# E-P-204-R3.net
KiCad netlist of a schematic drawn in EAGLE
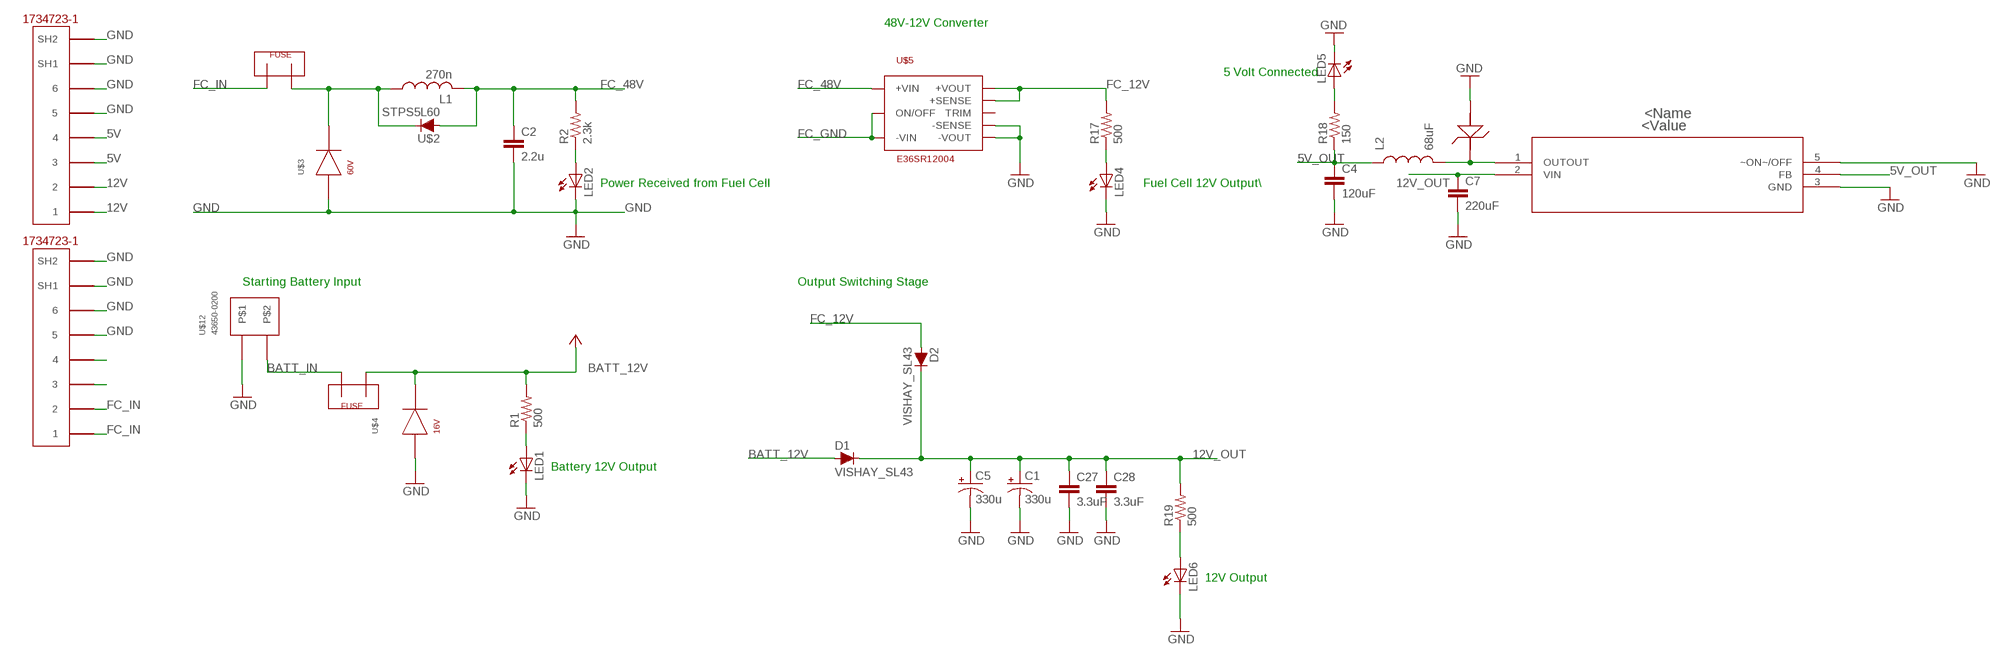
[diagram p0: schematic, sheet 1]

(export (version "E")
  (design (tool "Eeschema 10.0.6"))
  (components
    (comp (ref "C1")
      (value "330u")
      (footprint "eagle-import:PANASONIC_E")
      (libsource (lib "eagle-import") (part "CAP_POLE"))
    )
    (comp (ref "C2")
      (value "2.2u")
      (footprint "eagle-import:C1210")
      (libsource (lib "eagle-import") (part "C-EUC1210"))
    )
    (comp (ref "C4")
      (value "120uF")
      (footprint "eagle-import:0805")
      (libsource (lib "eagle-import") (part "CAP0805"))
    )
    (comp (ref "C5")
      (value "330u")
      (footprint "eagle-import:PANASONIC_E")
      (libsource (lib "eagle-import") (part "CAP_POLE"))
    )
    (comp (ref "C7")
      (value "220uF")
      (footprint "eagle-import:0805")
      (libsource (lib "eagle-import") (part "CAP0805"))
    )
    (comp (ref "C27")
      (value "3.3uF")
      (footprint "eagle-import:C0805K")
      (libsource (lib "eagle-import") (part "C-EUC0805K"))
    )
    (comp (ref "C28")
      (value "3.3uF")
      (footprint "eagle-import:C0805K")
      (libsource (lib "eagle-import") (part "C-EUC0805K"))
    )
    (comp (ref "D1")
      (value "VISHAY_SL43")
      (footprint "eagle-import:DO-214AB_SMC")
      (libsource (lib "eagle-import") (part "VISHAY_SL43"))
    )
    (comp (ref "D2")
      (value "VISHAY_SL43")
      (footprint "eagle-import:DO-214AB_SMC")
      (libsource (lib "eagle-import") (part "VISHAY_SL43"))
    )
    (comp (ref "L1")
      (value "270n")
      (footprint "eagle-import:L3225P")
      (libsource (lib "eagle-import") (part "L-USL3225P"))
    )
    (comp (ref "L2")
      (value "68uF")
      (footprint "eagle-import:0805")
      (libsource (lib "eagle-import") (part "INDUCTOR0805"))
    )
    (comp (ref "LED1")
      (value "LED1206")
      (footprint "eagle-import:LED-1206")
      (libsource (lib "eagle-import") (part "LED1206"))
    )
    (comp (ref "LED2")
      (value "LED1206")
      (footprint "eagle-import:LED-1206")
      (libsource (lib "eagle-import") (part "LED1206"))
    )
    (comp (ref "LED4")
      (value "LED1206")
      (footprint "eagle-import:LED-1206")
      (libsource (lib "eagle-import") (part "LED1206"))
    )
    (comp (ref "LED5")
      (value "LED1206")
      (footprint "eagle-import:LED-1206")
      (libsource (lib "eagle-import") (part "LED1206"))
    )
    (comp (ref "LED6")
      (value "LED1206")
      (footprint "eagle-import:LED-1206")
      (libsource (lib "eagle-import") (part "LED1206"))
    )
    (comp (ref "R1")
      (value "500")
      (footprint "eagle-import:M0805")
      (libsource (lib "eagle-import") (part "R-US_M0805"))
    )
    (comp (ref "R2")
      (value "2.3k")
      (footprint "eagle-import:M0805")
      (libsource (lib "eagle-import") (part "R-US_M0805"))
    )
    (comp (ref "R17")
      (value "500")
      (footprint "eagle-import:M0805")
      (libsource (lib "eagle-import") (part "R-US_M0805"))
    )
    (comp (ref "R18")
      (value "150")
      (footprint "eagle-import:M0805")
      (libsource (lib "eagle-import") (part "R-US_M0805"))
    )
    (comp (ref "R19")
      (value "500")
      (footprint "eagle-import:M0805")
      (libsource (lib "eagle-import") (part "R-US_M0805"))
    )
    (comp (ref "U$2")
      (value "STPS5L60")
      (footprint "eagle-import:STM_SMC")
      (libsource (lib "eagle-import") (part "STPS5L60"))
    )
    (comp (ref "U$3")
      (value "SMBJ60CA")
      (footprint "eagle-import:.277X.089")
      (libsource (lib "eagle-import") (part "SMBJ60CA"))
    )
    (comp (ref "U$4")
      (value "SMAJ16CA")
      (footprint "eagle-import:.25X.07")
      (libsource (lib "eagle-import") (part "SMAJ16CA"))
    )
    (comp (ref "U$5")
      (value "E36SR12004")
      (footprint "eagle-import:2.30X0.90X0.34")
      (libsource (lib "eagle-import") (part "E36SR12004"))
    )
    (comp (ref "U$6")
      (value "5555140-6")
      (footprint "eagle-import:1734723-1_RJ11")
      (libsource (lib "eagle-import") (part "5555140-6"))
    )
    (comp (ref "U$7")
      (value "FUSEMINI-BLADE")
      (footprint "eagle-import:MINI-BLADE-FUSE")
      (libsource (lib "eagle-import") (part "FUSEMINI-BLADE"))
    )
    (comp (ref "U$8")
      (value "LM2595T-5.0")
      (footprint "eagle-import:T05D")
      (fields
        (field (name "MANUFACTURER_PART_NUMBER") "LM2595T50")
        (field (name "COPYRIGHT") "Copyright C 2015 Accelerated Designs. All rights reserved")
      )
      (libsource (lib "eagle-import") (part "LM2595T-5.0"))
    )
    (comp (ref "U$9")
      (value "MURS120T3G")
      (footprint "eagle-import:MURS120T3G")
      (libsource (lib "eagle-import") (part "MURS120T3G"))
    )
    (comp (ref "U$10")
      (value "FUSEMINI-BLADE")
      (footprint "eagle-import:MINI-BLADE-FUSE")
      (libsource (lib "eagle-import") (part "FUSEMINI-BLADE"))
    )
    (comp (ref "U$11")
      (value "5555140-6")
      (footprint "eagle-import:1734723-1_RJ11")
      (libsource (lib "eagle-import") (part "5555140-6"))
    )
    (comp (ref "U$12")
      (value "43650-0200")
      (footprint "eagle-import:43650-0200")
      (libsource (lib "eagle-import") (part "43650-0200"))
    )
  )
  (nets
    (net (code "1") (name "+5V") (class "Default")
      (node (ref "D1") (pin "A") (pinfunction "A_A") (pintype "passive"))
      (node (ref "R1") (pin "2") (pinfunction "2_2") (pintype "passive"))
      (node (ref "U$10") (pin "OUT") (pinfunction "OUT_OUT") (pintype "bidirectional"))
      (node (ref "U$4") (pin "CATHODE") (pinfunction "CATHODE_CATHODE") (pintype "bidirectional"))
    )
    (net (code "2") (name "/5V") (class "Default")
      (node (ref "U$11") (pin "3") (pinfunction "3_3") (pintype "bidirectional"))
      (node (ref "U$11") (pin "4") (pinfunction "4_4") (pintype "bidirectional"))
    )
    (net (code "3") (name "/5V_OUT") (class "Default")
      (node (ref "C4") (pin "1") (pinfunction "1_1") (pintype "passive"))
      (node (ref "L2") (pin "1") (pinfunction "1_1") (pintype "passive"))
      (node (ref "R18") (pin "1") (pinfunction "1_1") (pintype "passive"))
      (node (ref "U$8") (pin "4") (pinfunction "FB_4") (pintype "passive"))
    )
    (net (code "4") (name "/12V") (class "Default")
      (node (ref "U$11") (pin "1") (pinfunction "1_1") (pintype "bidirectional"))
      (node (ref "U$11") (pin "2") (pinfunction "2_2") (pintype "bidirectional"))
    )
    (net (code "5") (name "/12V_OUT") (class "Default")
      (node (ref "C1") (pin "+") (pinfunction "+_+") (pintype "passive"))
      (node (ref "C27") (pin "1") (pinfunction "1_1") (pintype "passive"))
      (node (ref "C28") (pin "1") (pinfunction "1_1") (pintype "passive"))
      (node (ref "C5") (pin "+") (pinfunction "+_+") (pintype "passive"))
      (node (ref "C7") (pin "1") (pinfunction "1_1") (pintype "passive"))
      (node (ref "D1") (pin "C") (pinfunction "C_C") (pintype "passive"))
      (node (ref "D2") (pin "C") (pinfunction "C_C") (pintype "passive"))
      (node (ref "R19") (pin "2") (pinfunction "2_2") (pintype "passive"))
      (node (ref "U$8") (pin "2") (pinfunction "VIN_2") (pintype "input"))
    )
    (net (code "6") (name "/BATT_IN") (class "Default")
      (node (ref "U$10") (pin "IN") (pinfunction "IN_IN") (pintype "bidirectional"))
      (node (ref "U$12") (pin "P$1") (pinfunction "P$2_P$1") (pintype "bidirectional"))
    )
    (net (code "7") (name "/FC_12V") (class "Default")
      (node (ref "D2") (pin "A") (pinfunction "A_A") (pintype "passive"))
      (node (ref "R17") (pin "2") (pinfunction "2_2") (pintype "passive"))
      (node (ref "U$5") (pin "P$7") (pinfunction "+SENSE_P$7") (pintype "input"))
      (node (ref "U$5") (pin "P$8") (pinfunction "+VOUT_P$8") (pintype "power_in"))
    )
    (net (code "8") (name "/FC_48V") (class "Default")
      (node (ref "C2") (pin "1") (pinfunction "1_1") (pintype "passive"))
      (node (ref "L1") (pin "2") (pinfunction "2_2") (pintype "passive"))
      (node (ref "R2") (pin "2") (pinfunction "2_2") (pintype "passive"))
      (node (ref "U$2") (pin "A") (pinfunction "A_A") (pintype "passive"))
      (node (ref "U$5") (pin "P$1") (pinfunction "+VIN_P$1") (pintype "power_in"))
    )
    (net (code "9") (name "/FC_GND") (class "Default")
      (node (ref "U$5") (pin "P$2") (pinfunction "ON/OFF_P$2") (pintype "bidirectional"))
      (node (ref "U$5") (pin "P$3") (pinfunction "-VIN_P$3") (pintype "power_in"))
    )
    (net (code "10") (name "/FC_IN") (class "Default")
      (node (ref "U$6") (pin "1") (pinfunction "1_1") (pintype "bidirectional"))
      (node (ref "U$6") (pin "2") (pinfunction "2_2") (pintype "bidirectional"))
      (node (ref "U$7") (pin "OUT") (pinfunction "OUT_OUT") (pintype "bidirectional"))
    )
    (net (code "11") (name "GND") (class "Default")
      (node (ref "C1") (pin "-") (pinfunction "-_-") (pintype "passive"))
      (node (ref "C2") (pin "2") (pinfunction "2_2") (pintype "passive"))
      (node (ref "C27") (pin "2") (pinfunction "2_2") (pintype "passive"))
      (node (ref "C28") (pin "2") (pinfunction "2_2") (pintype "passive"))
      (node (ref "C4") (pin "2") (pinfunction "2_2") (pintype "passive"))
      (node (ref "C5") (pin "-") (pinfunction "-_-") (pintype "passive"))
      (node (ref "C7") (pin "2") (pinfunction "2_2") (pintype "passive"))
      (node (ref "LED1") (pin "C") (pinfunction "C_C") (pintype "passive"))
      (node (ref "LED2") (pin "C") (pinfunction "C_C") (pintype "passive"))
      (node (ref "LED4") (pin "C") (pinfunction "C_C") (pintype "passive"))
      (node (ref "LED5") (pin "C") (pinfunction "C_C") (pintype "passive"))
      (node (ref "LED6") (pin "C") (pinfunction "C_C") (pintype "passive"))
      (node (ref "U$11") (pin "5") (pinfunction "5_5") (pintype "bidirectional"))
      (node (ref "U$11") (pin "6") (pinfunction "6_6") (pintype "bidirectional"))
      (node (ref "U$11") (pin "SH1") (pinfunction "SH1_SH1") (pintype "bidirectional"))
      (node (ref "U$11") (pin "SH2") (pinfunction "SH2_SH2") (pintype "bidirectional"))
      (node (ref "U$12") (pin "P$2") (pinfunction "P$1_P$2") (pintype "bidirectional"))
      (node (ref "U$3") (pin "ANODE") (pinfunction "ANODE_ANODE") (pintype "bidirectional"))
      (node (ref "U$4") (pin "ANODE") (pinfunction "ANODE_ANODE") (pintype "bidirectional"))
      (node (ref "U$5") (pin "P$4") (pinfunction "-VOUT_P$4") (pintype "power_in"))
      (node (ref "U$5") (pin "P$5") (pinfunction "-SENSE_P$5") (pintype "input"))
      (node (ref "U$6") (pin "5") (pinfunction "5_5") (pintype "bidirectional"))
      (node (ref "U$6") (pin "6") (pinfunction "6_6") (pintype "bidirectional"))
      (node (ref "U$6") (pin "SH1") (pinfunction "SH1_SH1") (pintype "bidirectional"))
      (node (ref "U$6") (pin "SH2") (pinfunction "SH2_SH2") (pintype "bidirectional"))
      (node (ref "U$8") (pin "3") (pinfunction "GND_3") (pintype "passive"))
      (node (ref "U$8") (pin "5") (pinfunction "~{ON}/OFF_5") (pintype "passive"))
      (node (ref "U$9") (pin "P$2") (pinfunction "PIN1_P$2") (pintype "bidirectional"))
    )
    (net (code "12") (name "Net-(L1-Pad1)") (class "Default")
      (node (ref "L1") (pin "1") (pinfunction "1_1") (pintype "passive"))
      (node (ref "U$2") (pin "C") (pinfunction "C_C") (pintype "passive"))
      (node (ref "U$3") (pin "CATHODE") (pinfunction "CATHODE_CATHODE") (pintype "bidirectional"))
      (node (ref "U$7") (pin "IN") (pinfunction "IN_IN") (pintype "bidirectional"))
    )
    (net (code "13") (name "Net-(LED1-PadA)") (class "Default")
      (node (ref "LED1") (pin "A") (pinfunction "A_A") (pintype "passive"))
      (node (ref "R1") (pin "1") (pinfunction "1_1") (pintype "passive"))
    )
    (net (code "14") (name "Net-(LED2-PadA)") (class "Default")
      (node (ref "LED2") (pin "A") (pinfunction "A_A") (pintype "passive"))
      (node (ref "R2") (pin "1") (pinfunction "1_1") (pintype "passive"))
    )
    (net (code "15") (name "Net-(LED4-PadA)") (class "Default")
      (node (ref "LED4") (pin "A") (pinfunction "A_A") (pintype "passive"))
      (node (ref "R17") (pin "1") (pinfunction "1_1") (pintype "passive"))
    )
    (net (code "16") (name "Net-(LED5-PadA)") (class "Default")
      (node (ref "LED5") (pin "A") (pinfunction "A_A") (pintype "passive"))
      (node (ref "R18") (pin "2") (pinfunction "2_2") (pintype "passive"))
    )
    (net (code "17") (name "Net-(LED6-PadA)") (class "Default")
      (node (ref "LED6") (pin "A") (pinfunction "A_A") (pintype "passive"))
      (node (ref "R19") (pin "1") (pinfunction "1_1") (pintype "passive"))
    )
    (net (code "18") (name "Net-(U$8-OUTOUT)") (class "Default")
      (node (ref "L2") (pin "2") (pinfunction "2_2") (pintype "passive"))
      (node (ref "U$8") (pin "1") (pinfunction "OUTOUT_1") (pintype "output"))
      (node (ref "U$9") (pin "P$1") (pinfunction "P$2_P$1") (pintype "bidirectional"))
    )
    (net (code "19") (name "unconnected-(U$5-TRIM-PadP$6)") (class "Default")
      (node (ref "U$5") (pin "P$6") (pinfunction "TRIM_P$6") (pintype "bidirectional"))
    )
    (net (code "20") (name "unconnected-(U$6-Pad3)") (class "Default")
      (node (ref "U$6") (pin "3") (pinfunction "3_3") (pintype "bidirectional"))
    )
    (net (code "21") (name "unconnected-(U$6-Pad4)") (class "Default")
      (node (ref "U$6") (pin "4") (pinfunction "4_4") (pintype "bidirectional"))
    )
  )
)
